# Smart_Stepper_Fin_-_Driver_-_DRV8825.net
KiCad netlist of a schematic drawn in Altium Designer
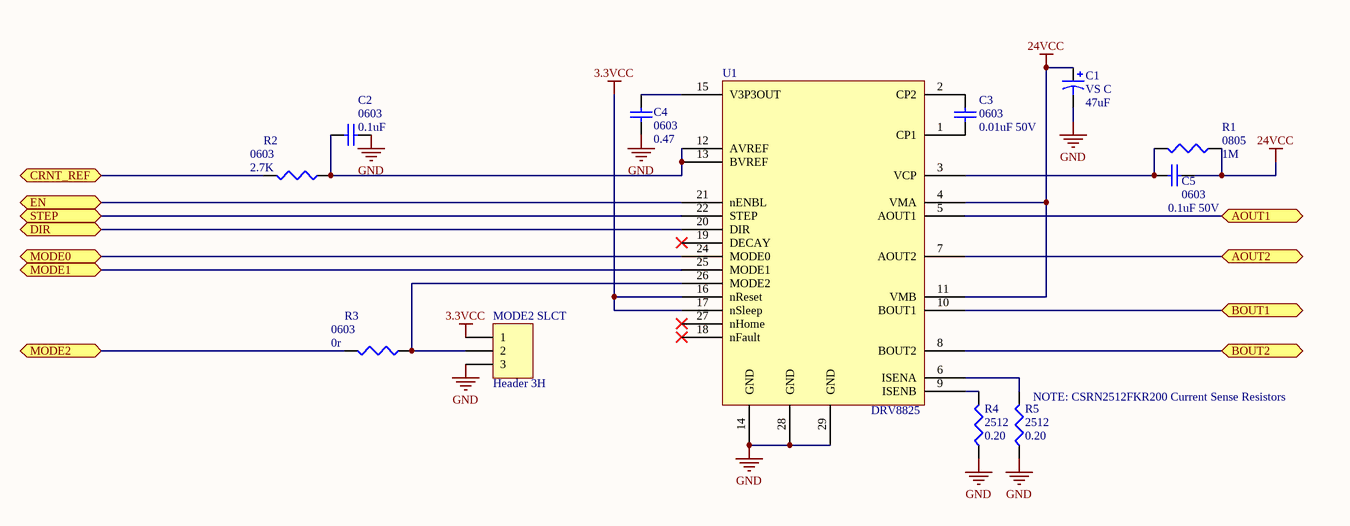
[diagram p0: Smart Stepper Fin - Driver - DRV8825.SchDoc]

(export (version "E")
  (design (tool "Eeschema 10.0.6"))
  (components
    (comp (ref "C1")
      (value "VS C")
      (footprint "Panasonic VS C")
      (description "Polarized Capacitor (Radial)")
      (fields (field (name "ALTIUM_VALUE") "47uF") (field (name "PUBLISHER") "Altium Limited"))
      (libsource (lib "Miscellaneous Devices") (part "Cap Pol1"))
    )
    (comp (ref "C2")
      (value "0603")
      (footprint "1608[0603]")
      (description "Capacitor (Semiconductor SIM Model)")
      (fields (field (name "ALTIUM_VALUE") "0.1uF") (field (name "PUBLISHER") "Altium Limited"))
      (libsource (lib "Miscellaneous Devices") (part "Cap Semi"))
    )
    (comp (ref "C3")
      (value "0603")
      (footprint "1608[0603]")
      (description "Capacitor (Semiconductor SIM Model)")
      (fields (field (name "ALTIUM_VALUE") "0.01uF 50V") (field (name "PUBLISHER") "Altium Limited"))
      (libsource (lib "Miscellaneous Devices") (part "Cap Semi"))
    )
    (comp (ref "C4")
      (value "0603")
      (footprint "1608[0603]")
      (description "Capacitor (Semiconductor SIM Model)")
      (fields (field (name "ALTIUM_VALUE") "0.47") (field (name "PUBLISHER") "Altium Limited"))
      (libsource (lib "Miscellaneous Devices") (part "Cap Semi"))
    )
    (comp (ref "C5")
      (value "0603")
      (footprint "1608[0603]")
      (description "Capacitor (Semiconductor SIM Model)")
      (fields (field (name "ALTIUM_VALUE") "0.1uF 50V") (field (name "PUBLISHER") "Altium Limited"))
      (libsource (lib "Miscellaneous Devices") (part "Cap Semi"))
    )
    (comp (ref "MODE2 SLCT")
      (value "Header 3H")
      (footprint "HDR1X3H")
      (description "Header, 3-Pin, Right Angle")
      (fields (field (name "PUBLISHER") "Altium Limited"))
      (libsource (lib "Miscellaneous Connectors") (part "Header 3H"))
    )
    (comp (ref "R1")
      (value "0805")
      (footprint "J1-0603")
      (description "Resistor")
      (fields (field (name "ALTIUM_VALUE") "1M") (field (name "PUBLISHER") "Altium Limited"))
      (libsource (lib "Miscellaneous Devices") (part "Res3"))
    )
    (comp (ref "R2")
      (value "0603")
      (footprint "J1-0603")
      (description "Resistor")
      (fields (field (name "ALTIUM_VALUE") "2.7K") (field (name "PUBLISHER") "Altium Limited"))
      (libsource (lib "Miscellaneous Devices") (part "Res3"))
    )
    (comp (ref "R3")
      (value "0603")
      (footprint "J1-0603")
      (description "Resistor")
      (fields (field (name "ALTIUM_VALUE") "0r") (field (name "PUBLISHER") "Altium Limited"))
      (libsource (lib "Miscellaneous Devices") (part "Res3"))
    )
    (comp (ref "R4")
      (value "2512")
      (footprint "Resistor2512")
      (description "Resistor")
      (fields (field (name "ALTIUM_VALUE") "0.20") (field (name "PUBLISHER") "Altium Limited"))
      (libsource (lib "Miscellaneous Devices") (part "Res3"))
    )
    (comp (ref "R5")
      (value "2512")
      (footprint "Resistor2512")
      (description "Resistor")
      (fields (field (name "ALTIUM_VALUE") "0.20") (field (name "PUBLISHER") "Altium Limited"))
      (libsource (lib "Miscellaneous Devices") (part "Res3"))
    )
    (comp (ref "U1")
      (value "DRV8825")
      (footprint "DRV8825")
      (description "DRV8825 Ti Stepper Driver")
      (libsource (lib "ExtruderFinLib") (part "DRV8825"))
    )
  )
  (nets
    (net (code "1") (name "/AOUT1") (class "Default")
      (node (ref "U1") (pin "5") (pinfunction "AOUT1_5") (pintype "passive"))
    )
    (net (code "2") (name "/AOUT2") (class "Default")
      (node (ref "U1") (pin "7") (pinfunction "AOUT2_7") (pintype "passive"))
    )
    (net (code "3") (name "/BOUT1") (class "Default")
      (node (ref "U1") (pin "10") (pinfunction "BOUT1_10") (pintype "passive"))
    )
    (net (code "4") (name "/BOUT2") (class "Default")
      (node (ref "U1") (pin "8") (pinfunction "BOUT2_8") (pintype "passive"))
    )
    (net (code "5") (name "/CRNT_REF") (class "Default")
      (node (ref "R2") (pin "2") (pinfunction "2_2") (pintype "passive"))
    )
    (net (code "6") (name "/DIR") (class "Default")
      (node (ref "U1") (pin "20") (pinfunction "DIR_20") (pintype "passive"))
    )
    (net (code "7") (name "/EN") (class "Default")
      (node (ref "U1") (pin "21") (pinfunction "nENBL_21") (pintype "passive"))
    )
    (net (code "8") (name "/MODE0") (class "Default")
      (node (ref "U1") (pin "24") (pinfunction "MODE0_24") (pintype "passive"))
    )
    (net (code "9") (name "/MODE1") (class "Default")
      (node (ref "U1") (pin "25") (pinfunction "MODE1_25") (pintype "passive"))
    )
    (net (code "10") (name "/MODE2") (class "Default")
      (node (ref "R3") (pin "2") (pinfunction "2_2") (pintype "passive"))
    )
    (net (code "11") (name "/STEP") (class "Default")
      (node (ref "U1") (pin "22") (pinfunction "STEP_22") (pintype "passive"))
    )
    (net (code "12") (name "3.3VCC") (class "Default")
      (node (ref "MODE2 SLCT") (pin "1") (pinfunction "1_1") (pintype "passive"))
      (node (ref "U1") (pin "16") (pinfunction "nReset_16") (pintype "passive"))
      (node (ref "U1") (pin "17") (pinfunction "nSleep_17") (pintype "passive"))
    )
    (net (code "13") (name "24VCC") (class "Default")
      (node (ref "C1") (pin "1") (pinfunction "1_1") (pintype "passive"))
      (node (ref "C5") (pin "1") (pinfunction "1_1") (pintype "passive"))
      (node (ref "R1") (pin "1") (pinfunction "1_1") (pintype "passive"))
      (node (ref "U1") (pin "11") (pinfunction "VMB_11") (pintype "passive"))
      (node (ref "U1") (pin "4") (pinfunction "VMA_4") (pintype "passive"))
    )
    (net (code "14") (name "GND") (class "Default")
      (node (ref "C1") (pin "2") (pinfunction "2_2") (pintype "passive"))
      (node (ref "C2") (pin "1") (pinfunction "1_1") (pintype "passive"))
      (node (ref "C4") (pin "1") (pinfunction "1_1") (pintype "passive"))
      (node (ref "MODE2 SLCT") (pin "3") (pinfunction "3_3") (pintype "passive"))
      (node (ref "R4") (pin "1") (pinfunction "1_1") (pintype "passive"))
      (node (ref "R5") (pin "1") (pinfunction "1_1") (pintype "passive"))
      (node (ref "U1") (pin "14") (pinfunction "GND_14") (pintype "passive"))
      (node (ref "U1") (pin "28") (pinfunction "GND_28") (pintype "passive"))
      (node (ref "U1") (pin "29") (pinfunction "GND_29") (pintype "passive"))
    )
    (net (code "15") (name "Net-(U1-AVREF)") (class "Default")
      (node (ref "C2") (pin "2") (pinfunction "2_2") (pintype "passive"))
      (node (ref "R2") (pin "1") (pinfunction "1_1") (pintype "passive"))
      (node (ref "U1") (pin "12") (pinfunction "AVREF_12") (pintype "passive"))
      (node (ref "U1") (pin "13") (pinfunction "BVREF_13") (pintype "passive"))
    )
    (net (code "16") (name "Net-(U1-CP1)") (class "Default")
      (node (ref "C3") (pin "1") (pinfunction "1_1") (pintype "passive"))
      (node (ref "U1") (pin "1") (pinfunction "CP1_1") (pintype "passive"))
    )
    (net (code "17") (name "Net-(U1-CP2)") (class "Default")
      (node (ref "C3") (pin "2") (pinfunction "2_2") (pintype "passive"))
      (node (ref "U1") (pin "2") (pinfunction "CP2_2") (pintype "passive"))
    )
    (net (code "18") (name "Net-(U1-ISENA)") (class "Default")
      (node (ref "R5") (pin "2") (pinfunction "2_2") (pintype "passive"))
      (node (ref "U1") (pin "6") (pinfunction "ISENA_6") (pintype "passive"))
    )
    (net (code "19") (name "Net-(U1-ISENB)") (class "Default")
      (node (ref "R4") (pin "2") (pinfunction "2_2") (pintype "passive"))
      (node (ref "U1") (pin "9") (pinfunction "ISENB_9") (pintype "passive"))
    )
    (net (code "20") (name "Net-(U1-MODE2)") (class "Default")
      (node (ref "MODE2 SLCT") (pin "2") (pinfunction "2_2") (pintype "passive"))
      (node (ref "R3") (pin "1") (pinfunction "1_1") (pintype "passive"))
      (node (ref "U1") (pin "26") (pinfunction "MODE2_26") (pintype "passive"))
    )
    (net (code "21") (name "Net-(U1-V3P3OUT)") (class "Default")
      (node (ref "C4") (pin "2") (pinfunction "2_2") (pintype "passive"))
      (node (ref "U1") (pin "15") (pinfunction "V3P3OUT_15") (pintype "passive"))
    )
    (net (code "22") (name "Net-(U1-VCP)") (class "Default")
      (node (ref "C5") (pin "2") (pinfunction "2_2") (pintype "passive"))
      (node (ref "R1") (pin "2") (pinfunction "2_2") (pintype "passive"))
      (node (ref "U1") (pin "3") (pinfunction "VCP_3") (pintype "passive"))
    )
    (net (code "23") (name "unconnected-(U1-DECAY-Pad19)") (class "Default")
      (node (ref "U1") (pin "19") (pinfunction "DECAY_19") (pintype "passive+no_connect"))
    )
    (net (code "24") (name "unconnected-(U1-NC-Pad23)") (class "Default")
      (node (ref "U1") (pin "23") (pinfunction "NC_23") (pintype "passive"))
    )
    (net (code "25") (name "unconnected-(U1-nFault-Pad18)") (class "Default")
      (node (ref "U1") (pin "18") (pinfunction "nFault_18") (pintype "passive+no_connect"))
    )
    (net (code "26") (name "unconnected-(U1-nHome-Pad27)") (class "Default")
      (node (ref "U1") (pin "27") (pinfunction "nHome_27") (pintype "passive+no_connect"))
    )
  )
)
